# PMSM_G474.net
KiCad netlist of a schematic drawn in Altium Designer
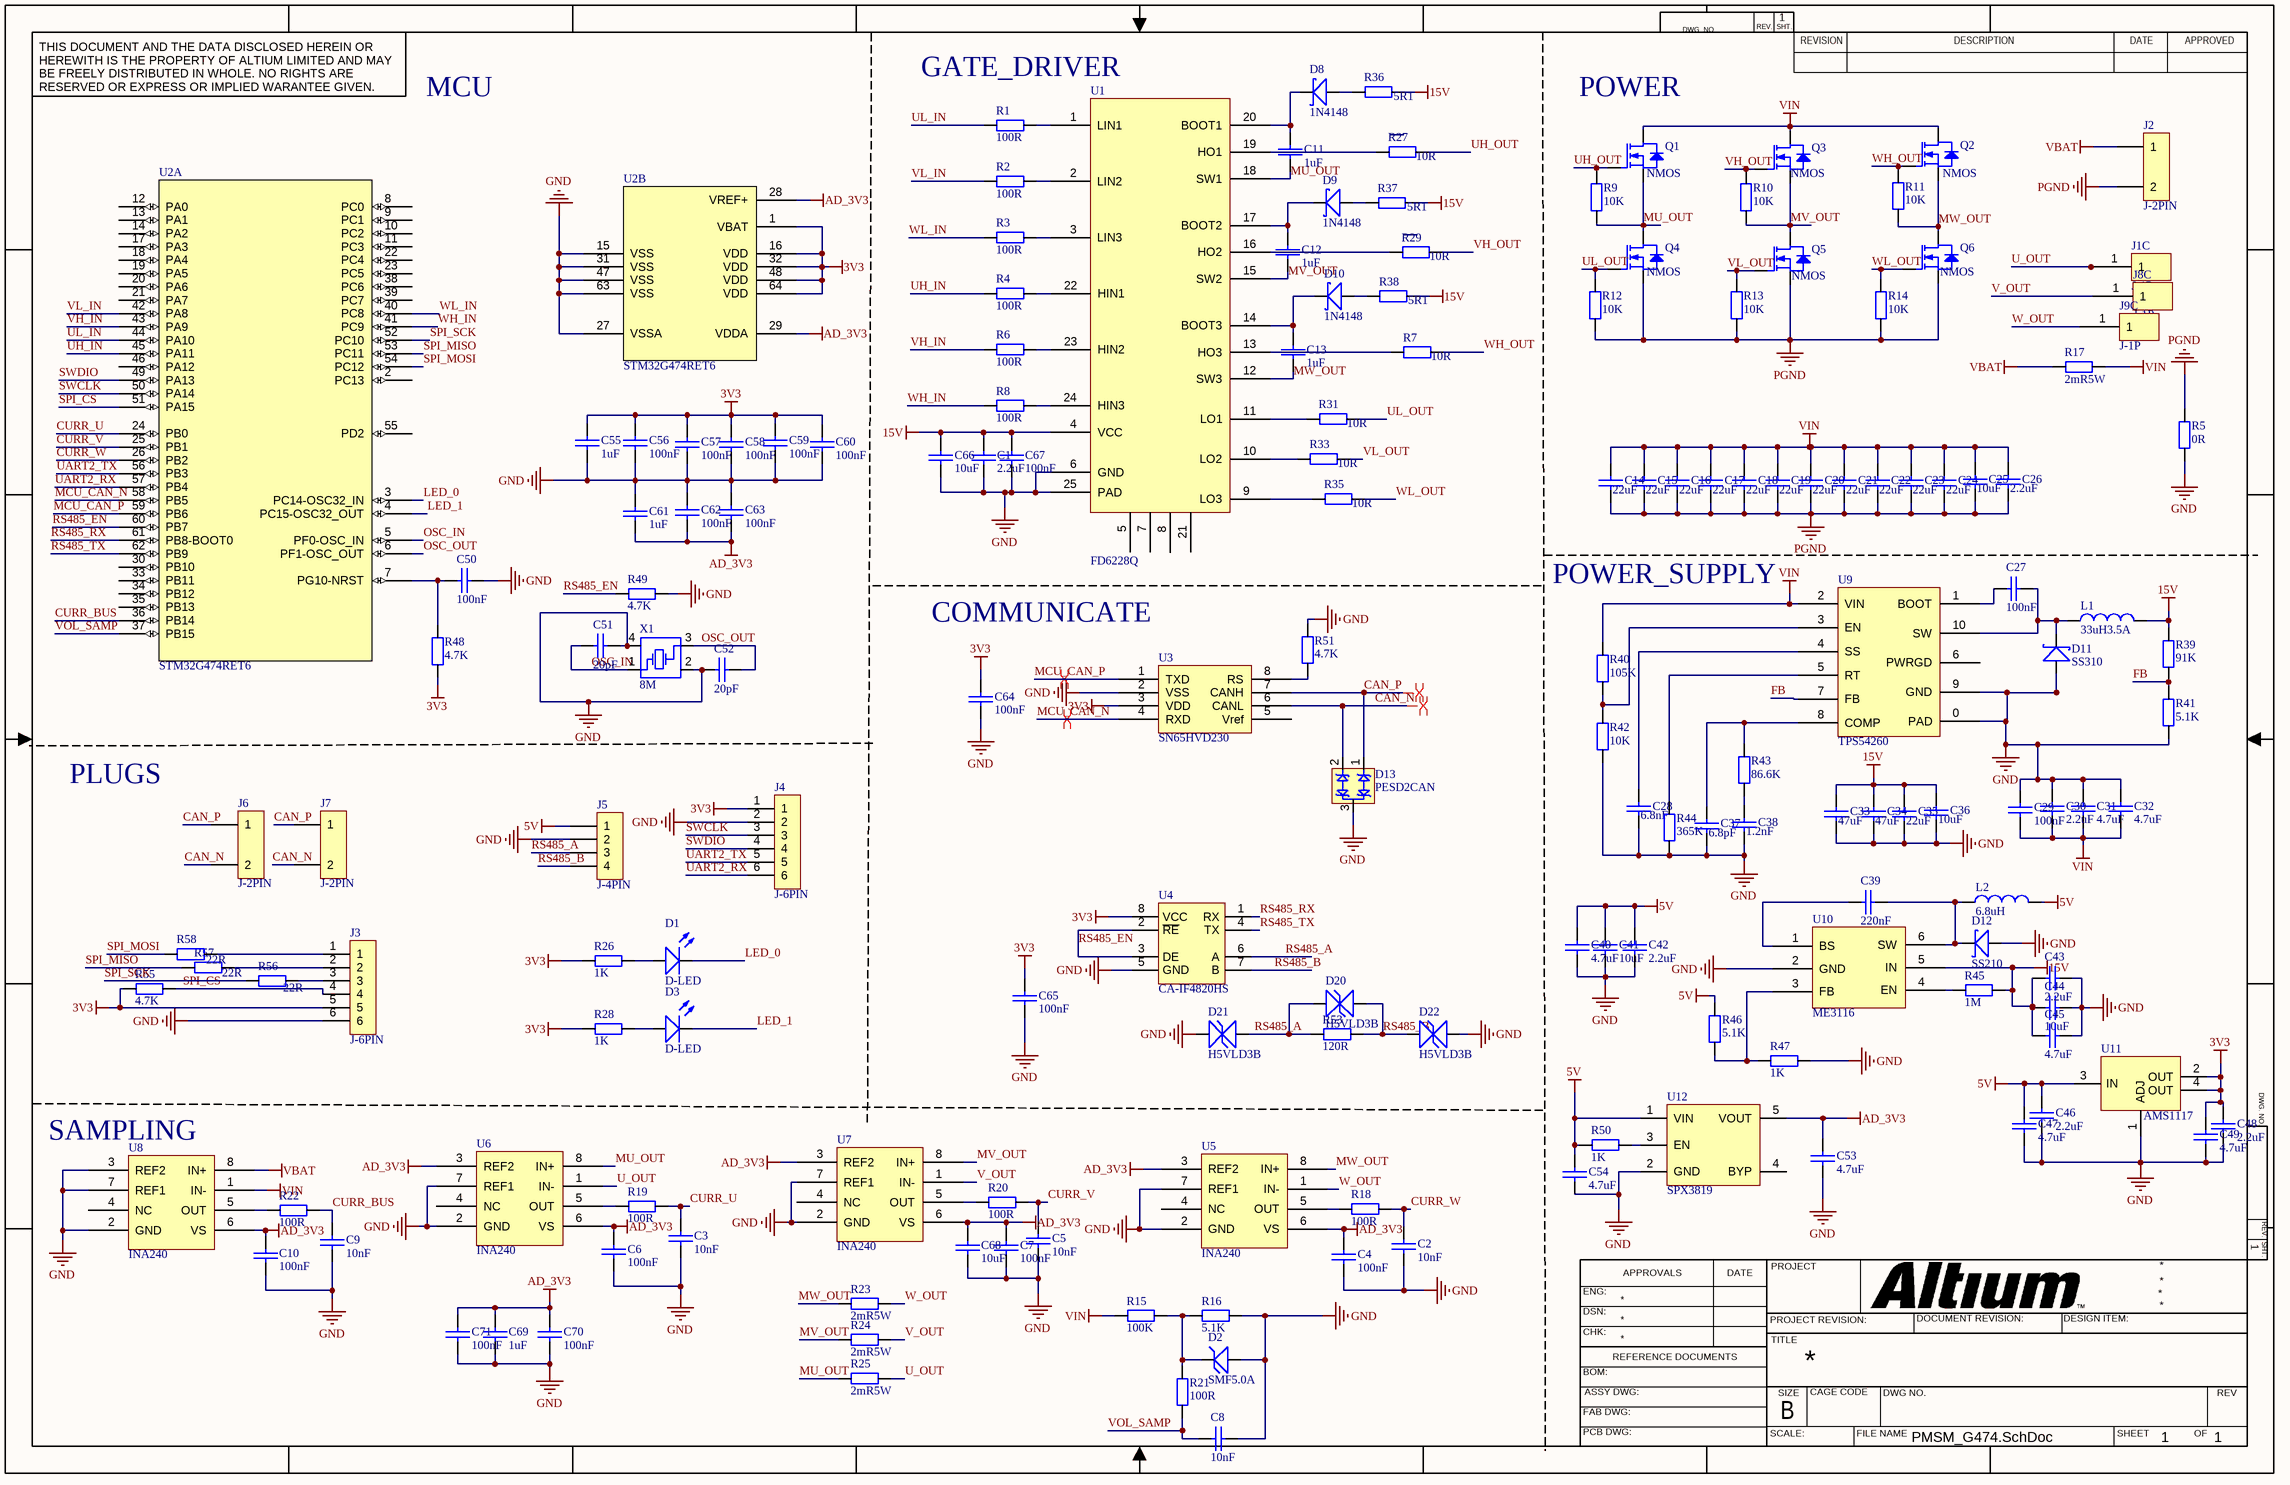
[diagram p0: PMSM_G474.SchDoc]

(export (version "E")
  (design (tool "Eeschema 10.0.6"))
  (components
    (comp (ref "C1")
      (value "2.2uF")
      (footprint "C-0603")
      (description "Non Polarised")
      (libsource (lib "ACTION_SchematicDiagramPack") (part "C"))
    )
    (comp (ref "C2")
      (value "10nF")
      (footprint "C-0603")
      (description "Non Polarised")
      (libsource (lib "ACTION_SchematicDiagramPack") (part "C"))
    )
    (comp (ref "C3")
      (value "10nF")
      (footprint "C-0603")
      (description "Non Polarised")
      (libsource (lib "ACTION_SchematicDiagramPack") (part "C"))
    )
    (comp (ref "C4")
      (value "100nF")
      (footprint "C-0603")
      (description "Non Polarised")
      (libsource (lib "ACTION_SchematicDiagramPack") (part "C"))
    )
    (comp (ref "C5")
      (value "10nF")
      (footprint "C-0603")
      (description "Non Polarised")
      (libsource (lib "ACTION_SchematicDiagramPack") (part "C"))
    )
    (comp (ref "C6")
      (value "100nF")
      (footprint "C-0603")
      (description "Non Polarised")
      (libsource (lib "ACTION_SchematicDiagramPack") (part "C"))
    )
    (comp (ref "C7")
      (value "100nF")
      (footprint "C-0603")
      (description "Non Polarised")
      (libsource (lib "ACTION_SchematicDiagramPack") (part "C"))
    )
    (comp (ref "C8")
      (value "10nF")
      (footprint "C-0603")
      (description "Non Polarised")
      (libsource (lib "ACTION_SchematicDiagramPack") (part "C"))
    )
    (comp (ref "C9")
      (value "10nF")
      (footprint "C-0603")
      (description "Non Polarised")
      (libsource (lib "ACTION_SchematicDiagramPack") (part "C"))
    )
    (comp (ref "C10")
      (value "100nF")
      (footprint "C-0603")
      (description "Non Polarised")
      (libsource (lib "ACTION_SchematicDiagramPack") (part "C"))
    )
    (comp (ref "C11")
      (value "1uF")
      (footprint "C-0603")
      (description "Non Polarised")
      (libsource (lib "ACTION_SchematicDiagramPack") (part "C"))
    )
    (comp (ref "C12")
      (value "1uF")
      (footprint "C-0603")
      (description "Non Polarised")
      (libsource (lib "ACTION_SchematicDiagramPack") (part "C"))
    )
    (comp (ref "C13")
      (value "1uF")
      (footprint "C-0603")
      (description "Non Polarised")
      (libsource (lib "ACTION_SchematicDiagramPack") (part "C"))
    )
    (comp (ref "C14")
      (value "22uF")
      (footprint "C-1206")
      (description "Non Polarised")
      (libsource (lib "ACTION_SchematicDiagramPack") (part "C"))
    )
    (comp (ref "C15")
      (value "22uF")
      (footprint "C-1206")
      (description "Non Polarised")
      (libsource (lib "ACTION_SchematicDiagramPack") (part "C"))
    )
    (comp (ref "C16")
      (value "22uF")
      (footprint "C-1206")
      (description "Non Polarised")
      (libsource (lib "ACTION_SchematicDiagramPack") (part "C"))
    )
    (comp (ref "C17")
      (value "22uF")
      (footprint "C-1206")
      (description "Non Polarised")
      (libsource (lib "ACTION_SchematicDiagramPack") (part "C"))
    )
    (comp (ref "C18")
      (value "22uF")
      (footprint "C-1206")
      (description "Non Polarised")
      (libsource (lib "ACTION_SchematicDiagramPack") (part "C"))
    )
    (comp (ref "C19")
      (value "22uF")
      (footprint "C-1206")
      (description "Non Polarised")
      (libsource (lib "ACTION_SchematicDiagramPack") (part "C"))
    )
    (comp (ref "C20")
      (value "22uF")
      (footprint "C-1206")
      (description "Non Polarised")
      (libsource (lib "ACTION_SchematicDiagramPack") (part "C"))
    )
    (comp (ref "C21")
      (value "22uF")
      (footprint "C-1206")
      (description "Non Polarised")
      (libsource (lib "ACTION_SchematicDiagramPack") (part "C"))
    )
    (comp (ref "C22")
      (value "22uF")
      (footprint "C-1206")
      (description "Non Polarised")
      (libsource (lib "ACTION_SchematicDiagramPack") (part "C"))
    )
    (comp (ref "C23")
      (value "22uF")
      (footprint "C-1206")
      (description "Non Polarised")
      (libsource (lib "ACTION_SchematicDiagramPack") (part "C"))
    )
    (comp (ref "C24")
      (value "22uF")
      (footprint "C-1206")
      (description "Non Polarised")
      (libsource (lib "ACTION_SchematicDiagramPack") (part "C"))
    )
    (comp (ref "C25")
      (value "10uF")
      (footprint "C-1206")
      (description "Non Polarised")
      (libsource (lib "ACTION_SchematicDiagramPack") (part "C"))
    )
    (comp (ref "C26")
      (value "2.2uF")
      (footprint "C-1206")
      (description "Non Polarised")
      (libsource (lib "ACTION_SchematicDiagramPack") (part "C"))
    )
    (comp (ref "C27")
      (value "100nF")
      (footprint "C-0603")
      (description "Non Polarised")
      (libsource (lib "ACTION_SchematicDiagramPack") (part "C"))
    )
    (comp (ref "C28")
      (value "6.8nF")
      (footprint "C-0603")
      (description "Non Polarised")
      (libsource (lib "ACTION_SchematicDiagramPack") (part "C"))
    )
    (comp (ref "C29")
      (value "100nF")
      (footprint "C-0603")
      (description "Non Polarised")
      (libsource (lib "ACTION_SchematicDiagramPack") (part "C"))
    )
    (comp (ref "C30")
      (value "2.2uF")
      (footprint "C-1206")
      (description "Non Polarised")
      (libsource (lib "ACTION_SchematicDiagramPack") (part "C"))
    )
    (comp (ref "C31")
      (value "4.7uF")
      (footprint "C-1206")
      (description "Non Polarised")
      (libsource (lib "ACTION_SchematicDiagramPack") (part "C"))
    )
    (comp (ref "C32")
      (value "4.7uF")
      (footprint "C-1206")
      (description "Non Polarised")
      (libsource (lib "ACTION_SchematicDiagramPack") (part "C"))
    )
    (comp (ref "C33")
      (value "47uF")
      (footprint "C-1206")
      (description "Non Polarised")
      (libsource (lib "ACTION_SchematicDiagramPack") (part "C"))
    )
    (comp (ref "C34")
      (value "47uF")
      (footprint "C-1206")
      (description "Non Polarised")
      (libsource (lib "ACTION_SchematicDiagramPack") (part "C"))
    )
    (comp (ref "C35")
      (value "22uF")
      (footprint "C-1206")
      (description "Non Polarised")
      (libsource (lib "ACTION_SchematicDiagramPack") (part "C"))
    )
    (comp (ref "C36")
      (value "10uF")
      (footprint "C-1206")
      (description "Non Polarised")
      (libsource (lib "ACTION_SchematicDiagramPack") (part "C"))
    )
    (comp (ref "C37")
      (value "6.8pF")
      (footprint "C-0603")
      (description "Non Polarised")
      (libsource (lib "ACTION_SchematicDiagramPack") (part "C"))
    )
    (comp (ref "C38")
      (value "1.2nF")
      (footprint "C-0603")
      (description "Non Polarised")
      (libsource (lib "ACTION_SchematicDiagramPack") (part "C"))
    )
    (comp (ref "C39")
      (value "220nF")
      (footprint "C-0603")
      (description "Non Polarised")
      (libsource (lib "ACTION_SchematicDiagramPack") (part "C"))
    )
    (comp (ref "C40")
      (value "4.7uF")
      (footprint "C-1206")
      (description "Non Polarised")
      (libsource (lib "ACTION_SchematicDiagramPack") (part "C"))
    )
    (comp (ref "C41")
      (value "10uF")
      (footprint "C-1206")
      (description "Non Polarised")
      (libsource (lib "ACTION_SchematicDiagramPack") (part "C"))
    )
    (comp (ref "C42")
      (value "2.2uF")
      (footprint "C-1206")
      (description "Non Polarised")
      (libsource (lib "ACTION_SchematicDiagramPack") (part "C"))
    )
    (comp (ref "C43")
      (value "2.2uF")
      (footprint "C-1206")
      (description "Non Polarised")
      (libsource (lib "ACTION_SchematicDiagramPack") (part "C"))
    )
    (comp (ref "C44")
      (value "10uF")
      (footprint "C-1206")
      (description "Non Polarised")
      (libsource (lib "ACTION_SchematicDiagramPack") (part "C"))
    )
    (comp (ref "C45")
      (value "4.7uF")
      (footprint "C-1206")
      (description "Non Polarised")
      (libsource (lib "ACTION_SchematicDiagramPack") (part "C"))
    )
    (comp (ref "C46")
      (value "2.2uF")
      (footprint "C-0603")
      (description "Non Polarised")
      (libsource (lib "ACTION_SchematicDiagramPack") (part "C"))
    )
    (comp (ref "C47")
      (value "4.7uF")
      (footprint "C-0603")
      (description "Non Polarised")
      (libsource (lib "ACTION_SchematicDiagramPack") (part "C"))
    )
    (comp (ref "C48")
      (value "2.2uF")
      (footprint "C-0603")
      (description "Non Polarised")
      (libsource (lib "ACTION_SchematicDiagramPack") (part "C"))
    )
    (comp (ref "C49")
      (value "4.7uF")
      (footprint "C-0603")
      (description "Non Polarised")
      (libsource (lib "ACTION_SchematicDiagramPack") (part "C"))
    )
    (comp (ref "C50")
      (value "100nF")
      (footprint "C-0603")
      (description "Non Polarised")
      (libsource (lib "ACTION_SchematicDiagramPack") (part "C"))
    )
    (comp (ref "C51")
      (value "20pF")
      (footprint "C-0603")
      (description "Non Polarised")
      (libsource (lib "ACTION_SchematicDiagramPack") (part "C"))
    )
    (comp (ref "C52")
      (value "20pF")
      (footprint "C-0603")
      (description "Non Polarised")
      (libsource (lib "ACTION_SchematicDiagramPack") (part "C"))
    )
    (comp (ref "C53")
      (value "4.7uF")
      (footprint "C-0603")
      (description "Non Polarised")
      (libsource (lib "ACTION_SchematicDiagramPack") (part "C"))
    )
    (comp (ref "C54")
      (value "4.7uF")
      (footprint "C-0603")
      (description "Non Polarised")
      (libsource (lib "ACTION_SchematicDiagramPack") (part "C"))
    )
    (comp (ref "C55")
      (value "1uF")
      (footprint "C-0603")
      (description "Non Polarised")
      (libsource (lib "ACTION_SchematicDiagramPack") (part "C"))
    )
    (comp (ref "C56")
      (value "100nF")
      (footprint "C-0603")
      (description "Non Polarised")
      (libsource (lib "ACTION_SchematicDiagramPack") (part "C"))
    )
    (comp (ref "C57")
      (value "100nF")
      (footprint "C-0603")
      (description "Non Polarised")
      (libsource (lib "ACTION_SchematicDiagramPack") (part "C"))
    )
    (comp (ref "C58")
      (value "100nF")
      (footprint "C-0603")
      (description "Non Polarised")
      (libsource (lib "ACTION_SchematicDiagramPack") (part "C"))
    )
    (comp (ref "C59")
      (value "100nF")
      (footprint "C-0603")
      (description "Non Polarised")
      (libsource (lib "ACTION_SchematicDiagramPack") (part "C"))
    )
    (comp (ref "C60")
      (value "100nF")
      (footprint "C-0603")
      (description "Non Polarised")
      (libsource (lib "ACTION_SchematicDiagramPack") (part "C"))
    )
    (comp (ref "C61")
      (value "1uF")
      (footprint "C-0603")
      (description "Non Polarised")
      (libsource (lib "ACTION_SchematicDiagramPack") (part "C"))
    )
    (comp (ref "C62")
      (value "100nF")
      (footprint "C-0603")
      (description "Non Polarised")
      (libsource (lib "ACTION_SchematicDiagramPack") (part "C"))
    )
    (comp (ref "C63")
      (value "100nF")
      (footprint "C-0603")
      (description "Non Polarised")
      (libsource (lib "ACTION_SchematicDiagramPack") (part "C"))
    )
    (comp (ref "C64")
      (value "100nF")
      (footprint "C-0603")
      (description "Non Polarised")
      (libsource (lib "ACTION_SchematicDiagramPack") (part "C"))
    )
    (comp (ref "C65")
      (value "100nF")
      (footprint "C-0603")
      (description "Non Polarised")
      (libsource (lib "ACTION_SchematicDiagramPack") (part "C"))
    )
    (comp (ref "C66")
      (value "10uF")
      (footprint "C-0603")
      (description "Non Polarised")
      (libsource (lib "ACTION_SchematicDiagramPack") (part "C"))
    )
    (comp (ref "C67")
      (value "100nF")
      (footprint "C-0603")
      (description "Non Polarised")
      (libsource (lib "ACTION_SchematicDiagramPack") (part "C"))
    )
    (comp (ref "C68")
      (value "10uF")
      (footprint "C-0603")
      (description "Non Polarised")
      (libsource (lib "ACTION_SchematicDiagramPack") (part "C"))
    )
    (comp (ref "C69")
      (value "1uF")
      (footprint "C-0603")
      (description "Non Polarised")
      (libsource (lib "ACTION_SchematicDiagramPack") (part "C"))
    )
    (comp (ref "C70")
      (value "100nF")
      (footprint "C-0603")
      (description "Non Polarised")
      (libsource (lib "ACTION_SchematicDiagramPack") (part "C"))
    )
    (comp (ref "C71")
      (value "100nF")
      (footprint "C-0603")
      (description "Non Polarised")
      (libsource (lib "ACTION_SchematicDiagramPack") (part "C"))
    )
    (comp (ref "D1")
      (value "D-LED")
      (footprint "D-LED-0603Blue")
      (description "LED")
      (libsource (lib "ACTION_SchematicDiagramPack") (part "D-LED"))
    )
    (comp (ref "D2")
      (value "SMF5.0A")
      (footprint "D-SOD-123")
      (description "单向TVS")
      (libsource (lib "ACTION_SchematicDiagramPack") (part "D-TVS-U"))
    )
    (comp (ref "D3")
      (value "D-LED")
      (footprint "D-LED-0603Blue")
      (description "LED")
      (libsource (lib "ACTION_SchematicDiagramPack") (part "D-LED"))
    )
    (comp (ref "D8")
      (value "1N4148")
      (footprint "D-SOD-123")
      (description "Schottky")
      (libsource (lib "ACTION_SchematicDiagramPack") (part "D-Schottky"))
    )
    (comp (ref "D9")
      (value "1N4148")
      (footprint "D-SOD-123")
      (description "Schottky")
      (libsource (lib "ACTION_SchematicDiagramPack") (part "D-Schottky"))
    )
    (comp (ref "D10")
      (value "1N4148")
      (footprint "D-SOD-123")
      (description "Schottky")
      (libsource (lib "ACTION_SchematicDiagramPack") (part "D-Schottky"))
    )
    (comp (ref "D11")
      (value "SS310")
      (footprint "DO-214AC(SMA)")
      (description "Schottky")
      (libsource (lib "ACTION_SchematicDiagramPack") (part "D-Schottky"))
    )
    (comp (ref "D12")
      (value "SS210")
      (footprint "DO-214AC(SMA)")
      (description "Schottky")
      (libsource (lib "ACTION_SchematicDiagramPack") (part "D-Schottky"))
    )
    (comp (ref "D13")
      (value "PESD2CAN")
      (footprint "SOT-233")
      (description "组合ESD二极管")
      (libsource (lib "ACTION_SchematicDiagramPack") (part "D-ESD"))
    )
    (comp (ref "D20")
      (value "H5VLD3B")
      (footprint "D-SOD-323")
      (description "双向TVS")
      (libsource (lib "ACTION_SchematicDiagramPack") (part "D-TVS-B"))
    )
    (comp (ref "D21")
      (value "H5VLD3B")
      (footprint "D-SOD-323")
      (description "双向TVS")
      (libsource (lib "ACTION_SchematicDiagramPack") (part "D-TVS-B"))
    )
    (comp (ref "D22")
      (value "H5VLD3B")
      (footprint "D-SOD-323")
      (description "双向TVS")
      (libsource (lib "ACTION_SchematicDiagramPack") (part "D-TVS-B"))
    )
    (comp (ref "J1")
      (value "J-1P")
      (footprint "PAD-1")
      (libsource (lib "ACTION_SchematicDiagramPack") (part "J-1P"))
    )
    (comp (ref "J2")
      (value "J-2PIN")
      (footprint "J-XT30-2P-F")
      (libsource (lib "ACTION_SchematicDiagramPack") (part "J-2PIN"))
    )
    (comp (ref "J3")
      (value "J-6PIN")
      (footprint "J-GH-6P")
      (libsource (lib "ACTION_SchematicDiagramPack") (part "J-6PIN"))
    )
    (comp (ref "J4")
      (value "J-6PIN")
      (footprint "J-GH-6P")
      (libsource (lib "ACTION_SchematicDiagramPack") (part "J-6PIN"))
    )
    (comp (ref "J5")
      (value "J-4PIN")
      (footprint "J-GH-4P")
      (fields (field (name "PUBLISHER") "Altium Limited"))
      (libsource (lib "ACTION_SchematicDiagramPack") (part "J-4PIN"))
    )
    (comp (ref "J6")
      (value "J-2PIN")
      (footprint "J-GH-2P")
      (libsource (lib "ACTION_SchematicDiagramPack") (part "J-2PIN"))
    )
    (comp (ref "J7")
      (value "J-2PIN")
      (footprint "J-GH-2P")
      (libsource (lib "ACTION_SchematicDiagramPack") (part "J-2PIN"))
    )
    (comp (ref "J8")
      (value "J-1P")
      (footprint "PAD-1")
      (libsource (lib "ACTION_SchematicDiagramPack") (part "J-1P"))
    )
    (comp (ref "J9")
      (value "J-1P")
      (footprint "PAD-1")
      (libsource (lib "ACTION_SchematicDiagramPack") (part "J-1P"))
    )
    (comp (ref "L1")
      (value "33uH3.5A")
      (footprint "L-SMD-7.0*7.0")
      (description "Inductor")
      (libsource (lib "ACTION_SchematicDiagramPack") (part "L-SMD"))
    )
    (comp (ref "L2")
      (value "6.8uH")
      (footprint "L-SMD-5.0*5.0*4.0")
      (description "Inductor")
      (libsource (lib "ACTION_SchematicDiagramPack") (part "L-SMD"))
    )
    (comp (ref "Q1")
      (value "NMOS")
      (footprint "SO-8FL  5*6")
      (libsource (lib "ACTION_SchematicDiagramPack") (part "NMOS"))
    )
    (comp (ref "Q2")
      (value "NMOS")
      (footprint "SO-8FL  5*6")
      (libsource (lib "ACTION_SchematicDiagramPack") (part "NMOS"))
    )
    (comp (ref "Q3")
      (value "NMOS")
      (footprint "SO-8FL  5*6")
      (libsource (lib "ACTION_SchematicDiagramPack") (part "NMOS"))
    )
    (comp (ref "Q4")
      (value "NMOS")
      (footprint "SO-8FL  5*6")
      (libsource (lib "ACTION_SchematicDiagramPack") (part "NMOS"))
    )
    (comp (ref "Q5")
      (value "NMOS")
      (footprint "SO-8FL  5*6")
      (libsource (lib "ACTION_SchematicDiagramPack") (part "NMOS"))
    )
    (comp (ref "Q6")
      (value "NMOS")
      (footprint "SO-8FL  5*6")
      (libsource (lib "ACTION_SchematicDiagramPack") (part "NMOS"))
    )
    (comp (ref "R1")
      (value "100R")
      (footprint "R-0603")
      (description "Resistor")
      (libsource (lib "ACTION_SchematicDiagramPack") (part "R"))
    )
    (comp (ref "R2")
      (value "100R")
      (footprint "R-0603")
      (description "Resistor")
      (libsource (lib "ACTION_SchematicDiagramPack") (part "R"))
    )
    (comp (ref "R3")
      (value "100R")
      (footprint "R-0603")
      (description "Resistor")
      (libsource (lib "ACTION_SchematicDiagramPack") (part "R"))
    )
    (comp (ref "R4")
      (value "100R")
      (footprint "R-0603")
      (description "Resistor")
      (libsource (lib "ACTION_SchematicDiagramPack") (part "R"))
    )
    (comp (ref "R5")
      (value "0R")
      (footprint "R-0603")
      (description "Resistor")
      (libsource (lib "ACTION_SchematicDiagramPack") (part "R"))
    )
    (comp (ref "R6")
      (value "100R")
      (footprint "R-0603")
      (description "Resistor")
      (libsource (lib "ACTION_SchematicDiagramPack") (part "R"))
    )
    (comp (ref "R7")
      (value "10R")
      (footprint "R-0603")
      (description "Resistor")
      (libsource (lib "ACTION_SchematicDiagramPack") (part "R"))
    )
    (comp (ref "R8")
      (value "100R")
      (footprint "R-0603")
      (description "Resistor")
      (libsource (lib "ACTION_SchematicDiagramPack") (part "R"))
    )
    (comp (ref "R9")
      (value "10K")
      (footprint "R-0603")
      (description "Resistor")
      (libsource (lib "ACTION_SchematicDiagramPack") (part "R"))
    )
    (comp (ref "R10")
      (value "10K")
      (footprint "R-0603")
      (description "Resistor")
      (libsource (lib "ACTION_SchematicDiagramPack") (part "R"))
    )
    (comp (ref "R11")
      (value "10K")
      (footprint "R-0603")
      (description "Resistor")
      (libsource (lib "ACTION_SchematicDiagramPack") (part "R"))
    )
    (comp (ref "R12")
      (value "10K")
      (footprint "R-0603")
      (description "Resistor")
      (libsource (lib "ACTION_SchematicDiagramPack") (part "R"))
    )
    (comp (ref "R13")
      (value "10K")
      (footprint "R-0603")
      (description "Resistor")
      (libsource (lib "ACTION_SchematicDiagramPack") (part "R"))
    )
    (comp (ref "R14")
      (value "10K")
      (footprint "R-0603")
      (description "Resistor")
      (libsource (lib "ACTION_SchematicDiagramPack") (part "R"))
    )
    (comp (ref "R15")
      (value "100K")
      (footprint "R-0603")
      (description "Resistor")
      (libsource (lib "ACTION_SchematicDiagramPack") (part "R"))
    )
    (comp (ref "R16")
      (value "5.1K")
      (footprint "R-0603")
      (description "Resistor")
      (libsource (lib "ACTION_SchematicDiagramPack") (part "R"))
    )
    (comp (ref "R17")
      (value "2mR5W")
      (footprint "R-2512")
      (description "Resistor")
      (libsource (lib "ACTION_SchematicDiagramPack") (part "R"))
    )
    (comp (ref "R18")
      (value "100R")
      (footprint "R-0603")
      (description "Resistor")
      (libsource (lib "ACTION_SchematicDiagramPack") (part "R"))
    )
    (comp (ref "R19")
      (value "100R")
      (footprint "R-0603")
      (description "Resistor")
      (libsource (lib "ACTION_SchematicDiagramPack") (part "R"))
    )
    (comp (ref "R20")
      (value "100R")
      (footprint "R-0603")
      (description "Resistor")
      (libsource (lib "ACTION_SchematicDiagramPack") (part "R"))
    )
    (comp (ref "R21")
      (value "100R")
      (footprint "R-0603")
      (description "Resistor")
      (libsource (lib "ACTION_SchematicDiagramPack") (part "R"))
    )
    (comp (ref "R22")
      (value "100R")
      (footprint "R-0603")
      (description "Resistor")
      (libsource (lib "ACTION_SchematicDiagramPack") (part "R"))
    )
    (comp (ref "R23")
      (value "2mR5W")
      (footprint "R-2512")
      (description "Resistor")
      (libsource (lib "ACTION_SchematicDiagramPack") (part "R"))
    )
    (comp (ref "R24")
      (value "2mR5W")
      (footprint "R-2512")
      (description "Resistor")
      (libsource (lib "ACTION_SchematicDiagramPack") (part "R"))
    )
    (comp (ref "R25")
      (value "2mR5W")
      (footprint "R-2512")
      (description "Resistor")
      (libsource (lib "ACTION_SchematicDiagramPack") (part "R"))
    )
    (comp (ref "R26")
      (value "1K")
      (footprint "R-0603")
      (description "Resistor")
      (libsource (lib "ACTION_SchematicDiagramPack") (part "R"))
    )
    (comp (ref "R27")
      (value "10R")
      (footprint "R-0603")
      (description "Resistor")
      (libsource (lib "ACTION_SchematicDiagramPack") (part "R"))
    )
    (comp (ref "R28")
      (value "1K")
      (footprint "R-0603")
      (description "Resistor")
      (libsource (lib "ACTION_SchematicDiagramPack") (part "R"))
    )
    (comp (ref "R29")
      (value "10R")
      (footprint "R-0603")
      (description "Resistor")
      (libsource (lib "ACTION_SchematicDiagramPack") (part "R"))
    )
    (comp (ref "R31")
      (value "10R")
      (footprint "R-0603")
      (description "Resistor")
      (libsource (lib "ACTION_SchematicDiagramPack") (part "R"))
    )
    (comp (ref "R33")
      (value "10R")
      (footprint "R-0603")
      (description "Resistor")
      (libsource (lib "ACTION_SchematicDiagramPack") (part "R"))
    )
    (comp (ref "R35")
      (value "10R")
      (footprint "R-0603")
      (description "Resistor")
      (libsource (lib "ACTION_SchematicDiagramPack") (part "R"))
    )
    (comp (ref "R36")
      (value "5R1")
      (footprint "R-0603")
      (description "Resistor")
      (libsource (lib "ACTION_SchematicDiagramPack") (part "R"))
    )
    (comp (ref "R37")
      (value "5R1")
      (footprint "R-0603")
      (description "Resistor")
      (libsource (lib "ACTION_SchematicDiagramPack") (part "R"))
    )
    (comp (ref "R38")
      (value "5R1")
      (footprint "R-0603")
      (description "Resistor")
      (libsource (lib "ACTION_SchematicDiagramPack") (part "R"))
    )
    (comp (ref "R39")
      (value "91K")
      (footprint "R-0603")
      (description "Resistor")
      (libsource (lib "ACTION_SchematicDiagramPack") (part "R"))
    )
    (comp (ref "R40")
      (value "105K")
      (footprint "R-0603")
      (description "Resistor")
      (libsource (lib "ACTION_SchematicDiagramPack") (part "R"))
    )
    (comp (ref "R41")
      (value "5.1K")
      (footprint "R-0603")
      (description "Resistor")
      (libsource (lib "ACTION_SchematicDiagramPack") (part "R"))
    )
    (comp (ref "R42")
      (value "10K")
      (footprint "R-0603")
      (description "Resistor")
      (libsource (lib "ACTION_SchematicDiagramPack") (part "R"))
    )
    (comp (ref "R43")
      (value "86.6K")
      (footprint "R-0603")
      (description "Resistor")
      (libsource (lib "ACTION_SchematicDiagramPack") (part "R"))
    )
    (comp (ref "R44")
      (value "365K")
      (footprint "R-0603")
      (description "Resistor")
      (libsource (lib "ACTION_SchematicDiagramPack") (part "R"))
    )
    (comp (ref "R45")
      (value "1M")
      (footprint "R-0603")
      (description "Resistor")
      (libsource (lib "ACTION_SchematicDiagramPack") (part "R"))
    )
    (comp (ref "R46")
      (value "5.1K")
      (footprint "R-0603")
      (description "Resistor")
      (libsource (lib "ACTION_SchematicDiagramPack") (part "R"))
    )
    (comp (ref "R47")
      (value "1K")
      (footprint "R-0603")
      (description "Resistor")
      (libsource (lib "ACTION_SchematicDiagramPack") (part "R"))
    )
    (comp (ref "R48")
      (value "4.7K")
      (footprint "R-0603")
      (description "Resistor")
      (libsource (lib "ACTION_SchematicDiagramPack") (part "R"))
    )
    (comp (ref "R49")
      (value "4.7K")
      (footprint "R-0603")
      (description "Resistor")
      (libsource (lib "ACTION_SchematicDiagramPack") (part "R"))
    )
    (comp (ref "R50")
      (value "1K")
      (footprint "R-0603")
      (description "Resistor")
      (libsource (lib "ACTION_SchematicDiagramPack") (part "R"))
    )
    (comp (ref "R51")
      (value "4.7K")
      (footprint "R-0603")
      (description "Resistor")
      (libsource (lib "ACTION_SchematicDiagramPack") (part "R"))
    )
    (comp (ref "R53")
      (value "120R")
      (footprint "R-0603")
      (description "Resistor")
      (libsource (lib "ACTION_SchematicDiagramPack") (part "R"))
    )
    (comp (ref "R55")
      (value "4.7K")
      (footprint "R-0603")
      (description "Resistor")
      (libsource (lib "ACTION_SchematicDiagramPack") (part "R"))
    )
    (comp (ref "R56")
      (value "22R")
      (footprint "R-0603")
      (description "Resistor")
      (libsource (lib "ACTION_SchematicDiagramPack") (part "R"))
    )
    (comp (ref "R57")
      (value "22R")
      (footprint "R-0603")
      (description "Resistor")
      (libsource (lib "ACTION_SchematicDiagramPack") (part "R"))
    )
    (comp (ref "R58")
      (value "22R")
      (footprint "R-0603")
      (description "Resistor")
      (libsource (lib "ACTION_SchematicDiagramPack") (part "R"))
    )
    (comp (ref "U1")
      (value "FD6228Q")
      (footprint "QFN-24-4X4")
      (description "三相栅极驱动器")
      (libsource (lib "ACTION_SchematicDiagramPack") (part "FD6228Q"))
    )
    (comp (ref "U2")
      (value "STM32G474RET6")
      (footprint "STM-LQFP64_N")
      (libsource (lib "ACTION_SchematicDiagramPack") (part "STM32G474RET6"))
    )
    (comp (ref "U3")
      (value "SN65HVD230")
      (footprint "SOp-8")
      (libsource (lib "ACTION_SchematicDiagramPack") (part "SN65HVD230"))
    )
    (comp (ref "U4")
      (value "CA-IF4820HS")
      (footprint "SOIC-8(4mm)")
      (description "485 半双工 非隔离 ±15V共模 50M")
      (libsource (lib "ACTION_SchematicDiagramPack") (part "CA-IF4820HS"))
    )
    (comp (ref "U5")
      (value "INA240")
      (footprint "SOIC-8(4mm)")
      (description "具有PWM抑制功能的电流检测IC")
      (libsource (lib "ACTION_SchematicDiagramPack") (part "INA240"))
    )
    (comp (ref "U6")
      (value "INA240")
      (footprint "SOIC-8(4mm)")
      (description "具有PWM抑制功能的电流检测IC")
      (libsource (lib "ACTION_SchematicDiagramPack") (part "INA240"))
    )
    (comp (ref "U7")
      (value "INA240")
      (footprint "SOIC-8(4mm)")
      (description "具有PWM抑制功能的电流检测IC")
      (libsource (lib "ACTION_SchematicDiagramPack") (part "INA240"))
    )
    (comp (ref "U8")
      (value "INA240")
      (footprint "SOIC-8(4mm)")
      (description "具有PWM抑制功能的电流检测IC")
      (libsource (lib "ACTION_SchematicDiagramPack") (part "INA240"))
    )
    (comp (ref "U9")
      (value "TPS54260")
      (footprint "MSOP-10")
      (description "3.5V-60V 2A Step-Down DCDC Convertor")
      (libsource (lib "ACTION_SchematicDiagramPack") (part "TPS54260"))
    )
    (comp (ref "U10")
      (value "ME3116")
      (footprint "SOT-236")
      (description "DC-DC BUCK CONVERTER 40V VINmax 1A IOUTmax")
      (libsource (lib "ACTION_SchematicDiagramPack") (part "ME3116"))
    )
    (comp (ref "U11")
      (value "AMS1117")
      (footprint "SOT-89")
      (description "LDO")
      (libsource (lib "ACTION_SchematicDiagramPack") (part "AMS1117"))
    )
    (comp (ref "U12")
      (value "SPX3819")
      (footprint "SOT-235")
      (description "LDO")
      (libsource (lib "ACTION_SchematicDiagramPack") (part "SPX3819"))
    )
    (comp (ref "X1")
      (value "8M")
      (footprint "X-SMD-3225-4P")
      (description "Crystal Oscillator")
      (libsource (lib "ACTION_SchematicDiagramPack") (part "Crystal-4p"))
    )
  )
  (nets
    (net (code "1") (name "/CAN_N") (class "Default")
      (node (ref "D13") (pin "2") (pinfunction "2_2") (pintype "passive"))
      (node (ref "J6") (pin "2") (pinfunction "2_2") (pintype "passive"))
      (node (ref "J7") (pin "2") (pinfunction "2_2") (pintype "passive"))
      (node (ref "U3") (pin "6") (pinfunction "CANL_6") (pintype "passive"))
    )
    (net (code "2") (name "/CAN_P") (class "Default")
      (node (ref "D13") (pin "1") (pinfunction "1_1") (pintype "passive"))
      (node (ref "J6") (pin "1") (pinfunction "1_1") (pintype "passive"))
      (node (ref "J7") (pin "1") (pinfunction "1_1") (pintype "passive"))
      (node (ref "U3") (pin "7") (pinfunction "CANH_7") (pintype "passive"))
    )
    (net (code "3") (name "/CURR_BUS") (class "Default")
      (node (ref "C9") (pin "1") (pinfunction "1_1") (pintype "passive"))
      (node (ref "R22") (pin "1") (pintype "passive"))
      (node (ref "U2") (pin "36") (pinfunction "PB14_36") (pintype "bidirectional"))
    )
    (net (code "4") (name "/CURR_U") (class "Default")
      (node (ref "C3") (pin "1") (pinfunction "1_1") (pintype "passive"))
      (node (ref "R19") (pin "1") (pintype "passive"))
      (node (ref "U2") (pin "24") (pinfunction "PB0_24") (pintype "bidirectional"))
    )
    (net (code "5") (name "/CURR_V") (class "Default")
      (node (ref "C5") (pin "1") (pinfunction "1_1") (pintype "passive"))
      (node (ref "R20") (pin "1") (pintype "passive"))
      (node (ref "U2") (pin "25") (pinfunction "PB1_25") (pintype "bidirectional"))
    )
    (net (code "6") (name "/CURR_W") (class "Default")
      (node (ref "C2") (pin "1") (pinfunction "1_1") (pintype "passive"))
      (node (ref "R18") (pin "1") (pintype "passive"))
      (node (ref "U2") (pin "26") (pinfunction "PB2_26") (pintype "bidirectional"))
    )
    (net (code "7") (name "/FB") (class "Default")
      (node (ref "R39") (pin "1") (pintype "passive"))
      (node (ref "R41") (pin "2") (pintype "passive"))
      (node (ref "U9") (pin "7") (pinfunction "FB_7") (pintype "passive"))
    )
    (net (code "8") (name "/LED_0") (class "Default")
      (node (ref "D1") (pin "2") (pinfunction "2_2") (pintype "passive"))
      (node (ref "U2") (pin "3") (pinfunction "PC14-OSC32_IN_3") (pintype "bidirectional"))
    )
    (net (code "9") (name "/LED_1") (class "Default")
      (node (ref "D3") (pin "2") (pinfunction "2_2") (pintype "passive"))
      (node (ref "U2") (pin "4") (pinfunction "PC15-OSC32_OUT_4") (pintype "bidirectional"))
    )
    (net (code "10") (name "/MCU_CAN_N") (class "Default")
      (node (ref "U2") (pin "58") (pinfunction "PB5_58") (pintype "bidirectional"))
      (node (ref "U3") (pin "4") (pinfunction "RXD_4") (pintype "passive"))
    )
    (net (code "11") (name "/MCU_CAN_P") (class "Default")
      (node (ref "U2") (pin "59") (pinfunction "PB6_59") (pintype "bidirectional"))
      (node (ref "U3") (pin "1") (pinfunction "TXD_1") (pintype "passive"))
    )
    (net (code "12") (name "/MU_OUT") (class "Default")
      (node (ref "C11") (pin "2") (pinfunction "2_2") (pintype "passive"))
      (node (ref "Q1") (pin "3") (pinfunction "S_3") (pintype "passive"))
      (node (ref "Q4") (pin "2") (pinfunction "D_2") (pintype "passive"))
      (node (ref "R25") (pin "1") (pintype "passive"))
      (node (ref "R9") (pin "2") (pintype "passive"))
      (node (ref "U1") (pin "18") (pinfunction "SW1_18") (pintype "passive"))
      (node (ref "U6") (pin "8") (pinfunction "IN+_8") (pintype "passive"))
    )
    (net (code "13") (name "/MV_OUT") (class "Default")
      (node (ref "C12") (pin "2") (pinfunction "2_2") (pintype "passive"))
      (node (ref "Q3") (pin "3") (pinfunction "S_3") (pintype "passive"))
      (node (ref "Q5") (pin "2") (pinfunction "D_2") (pintype "passive"))
      (node (ref "R10") (pin "2") (pintype "passive"))
      (node (ref "R24") (pin "1") (pintype "passive"))
      (node (ref "U1") (pin "15") (pinfunction "SW2_15") (pintype "passive"))
      (node (ref "U7") (pin "8") (pinfunction "IN+_8") (pintype "passive"))
    )
    (net (code "14") (name "/MW_OUT") (class "Default")
      (node (ref "C13") (pin "2") (pinfunction "2_2") (pintype "passive"))
      (node (ref "Q2") (pin "3") (pinfunction "S_3") (pintype "passive"))
      (node (ref "Q6") (pin "2") (pinfunction "D_2") (pintype "passive"))
      (node (ref "R11") (pin "2") (pintype "passive"))
      (node (ref "R23") (pin "1") (pintype "passive"))
      (node (ref "U1") (pin "12") (pinfunction "SW3_12") (pintype "passive"))
      (node (ref "U5") (pin "8") (pinfunction "IN+_8") (pintype "passive"))
    )
    (net (code "15") (name "/OSC_IN") (class "Default")
      (node (ref "C51") (pin "2") (pinfunction "2_2") (pintype "passive"))
      (node (ref "U2") (pin "5") (pinfunction "PF0-OSC_IN_5") (pintype "bidirectional"))
      (node (ref "X1") (pin "1") (pinfunction "OSC1_1") (pintype "passive"))
    )
    (net (code "16") (name "/OSC_OUT") (class "Default")
      (node (ref "C52") (pin "2") (pinfunction "2_2") (pintype "passive"))
      (node (ref "U2") (pin "6") (pinfunction "PF1-OSC_OUT_6") (pintype "bidirectional"))
      (node (ref "X1") (pin "3") (pinfunction "OSC2_3") (pintype "passive"))
    )
    (net (code "17") (name "/RS485_A") (class "Default")
      (node (ref "D20") (pin "1") (pinfunction "A_1") (pintype "passive"))
      (node (ref "D21") (pin "2") (pinfunction "K_2") (pintype "passive"))
      (node (ref "J5") (pin "3") (pinfunction "3_3") (pintype "passive"))
      (node (ref "R53") (pin "2") (pintype "passive"))
      (node (ref "U4") (pin "6") (pinfunction "A_6") (pintype "passive"))
    )
    (net (code "18") (name "/RS485_B") (class "Default")
      (node (ref "D20") (pin "2") (pinfunction "K_2") (pintype "passive"))
      (node (ref "D22") (pin "2") (pinfunction "K_2") (pintype "passive"))
      (node (ref "J5") (pin "4") (pinfunction "4_4") (pintype "passive"))
      (node (ref "R53") (pin "1") (pintype "passive"))
      (node (ref "U4") (pin "7") (pinfunction "B_7") (pintype "passive"))
    )
    (net (code "19") (name "/RS485_EN") (class "Default")
      (node (ref "R49") (pin "2") (pintype "passive"))
      (node (ref "U2") (pin "60") (pinfunction "PB7_60") (pintype "bidirectional"))
      (node (ref "U4") (pin "2") (pinfunction "~{RE}_2") (pintype "passive"))
      (node (ref "U4") (pin "3") (pinfunction "DE_3") (pintype "passive"))
    )
    (net (code "20") (name "/RS485_RX") (class "Default")
      (node (ref "U2") (pin "61") (pinfunction "PB8-BOOT0_61") (pintype "bidirectional"))
      (node (ref "U4") (pin "1") (pinfunction "RX_1") (pintype "passive"))
    )
    (net (code "21") (name "/RS485_TX") (class "Default")
      (node (ref "U2") (pin "62") (pinfunction "PB9_62") (pintype "bidirectional"))
      (node (ref "U4") (pin "4") (pinfunction "TX_4") (pintype "passive"))
    )
    (net (code "22") (name "/SPI_CS") (class "Default")
      (node (ref "J3") (pin "4") (pinfunction "4_4") (pintype "passive"))
      (node (ref "R55") (pin "1") (pintype "passive"))
      (node (ref "U2") (pin "51") (pinfunction "PA15_51") (pintype "bidirectional"))
    )
    (net (code "23") (name "/SPI_MISO") (class "Default")
      (node (ref "R57") (pin "2") (pintype "passive"))
      (node (ref "U2") (pin "53") (pinfunction "PC11_53") (pintype "bidirectional"))
    )
    (net (code "24") (name "/SPI_MOSI") (class "Default")
      (node (ref "R58") (pin "2") (pintype "passive"))
      (node (ref "U2") (pin "54") (pinfunction "PC12_54") (pintype "bidirectional"))
    )
    (net (code "25") (name "/SPI_SCK") (class "Default")
      (node (ref "R56") (pin "2") (pintype "passive"))
      (node (ref "U2") (pin "52") (pinfunction "PC10_52") (pintype "bidirectional"))
    )
    (net (code "26") (name "/SWCLK") (class "Default")
      (node (ref "J4") (pin "3") (pinfunction "3_3") (pintype "passive"))
      (node (ref "U2") (pin "50") (pinfunction "PA14_50") (pintype "bidirectional"))
    )
    (net (code "27") (name "/SWDIO") (class "Default")
      (node (ref "J4") (pin "4") (pinfunction "4_4") (pintype "passive"))
      (node (ref "U2") (pin "49") (pinfunction "PA13_49") (pintype "bidirectional"))
    )
    (net (code "28") (name "/UART2_RX") (class "Default")
      (node (ref "J4") (pin "6") (pinfunction "6_6") (pintype "passive"))
      (node (ref "U2") (pin "57") (pinfunction "PB4_57") (pintype "bidirectional"))
    )
    (net (code "29") (name "/UART2_TX") (class "Default")
      (node (ref "J4") (pin "5") (pinfunction "5_5") (pintype "passive"))
      (node (ref "U2") (pin "56") (pinfunction "PB3_56") (pintype "bidirectional"))
    )
    (net (code "30") (name "/UH_IN") (class "Default")
      (node (ref "R4") (pin "2") (pintype "passive"))
      (node (ref "U2") (pin "45") (pinfunction "PA11_45") (pintype "bidirectional"))
    )
    (net (code "31") (name "/UH_OUT") (class "Default")
      (node (ref "Q1") (pin "1") (pinfunction "G_1") (pintype "passive"))
      (node (ref "R27") (pin "2") (pintype "passive"))
      (node (ref "R9") (pin "1") (pintype "passive"))
    )
    (net (code "32") (name "/UL_IN") (class "Default")
      (node (ref "R1") (pin "2") (pintype "passive"))
      (node (ref "U2") (pin "44") (pinfunction "PA10_44") (pintype "bidirectional"))
    )
    (net (code "33") (name "/UL_OUT") (class "Default")
      (node (ref "Q4") (pin "1") (pinfunction "G_1") (pintype "passive"))
      (node (ref "R12") (pin "1") (pintype "passive"))
      (node (ref "R31") (pin "2") (pintype "passive"))
    )
    (net (code "34") (name "/U_OUT") (class "Default")
      (node (ref "J1") (pin "1") (pinfunction "1_1") (pintype "passive"))
      (node (ref "R25") (pin "2") (pintype "passive"))
      (node (ref "U6") (pin "1") (pinfunction "IN-_1") (pintype "passive"))
    )
    (net (code "35") (name "/VH_IN") (class "Default")
      (node (ref "R6") (pin "2") (pintype "passive"))
      (node (ref "U2") (pin "43") (pinfunction "PA9_43") (pintype "bidirectional"))
    )
    (net (code "36") (name "/VH_OUT") (class "Default")
      (node (ref "Q3") (pin "1") (pinfunction "G_1") (pintype "passive"))
      (node (ref "R10") (pin "1") (pintype "passive"))
      (node (ref "R29") (pin "2") (pintype "passive"))
    )
    (net (code "37") (name "/VL_IN") (class "Default")
      (node (ref "R2") (pin "2") (pintype "passive"))
      (node (ref "U2") (pin "42") (pinfunction "PA8_42") (pintype "bidirectional"))
    )
    (net (code "38") (name "/VL_OUT") (class "Default")
      (node (ref "Q5") (pin "1") (pinfunction "G_1") (pintype "passive"))
      (node (ref "R13") (pin "1") (pintype "passive"))
      (node (ref "R33") (pin "2") (pintype "passive"))
    )
    (net (code "39") (name "/VOL_SAMP") (class "Default")
      (node (ref "C8") (pin "1") (pinfunction "1_1") (pintype "passive"))
      (node (ref "R21") (pin "2") (pintype "passive"))
      (node (ref "U2") (pin "37") (pinfunction "PB15_37") (pintype "bidirectional"))
    )
    (net (code "40") (name "/V_OUT") (class "Default")
      (node (ref "J8") (pin "1") (pinfunction "1_1") (pintype "passive"))
      (node (ref "R24") (pin "2") (pintype "passive"))
      (node (ref "U7") (pin "1") (pinfunction "IN-_1") (pintype "passive"))
    )
    (net (code "41") (name "/WH_IN") (class "Default")
      (node (ref "R8") (pin "2") (pintype "passive"))
      (node (ref "U2") (pin "41") (pinfunction "PC9_41") (pintype "bidirectional"))
    )
    (net (code "42") (name "/WH_OUT") (class "Default")
      (node (ref "Q2") (pin "1") (pinfunction "G_1") (pintype "passive"))
      (node (ref "R11") (pin "1") (pintype "passive"))
      (node (ref "R7") (pin "2") (pintype "passive"))
    )
    (net (code "43") (name "/WL_IN") (class "Default")
      (node (ref "R3") (pin "2") (pintype "passive"))
      (node (ref "U2") (pin "40") (pinfunction "PC8_40") (pintype "bidirectional"))
    )
    (net (code "44") (name "/WL_OUT") (class "Default")
      (node (ref "Q6") (pin "1") (pinfunction "G_1") (pintype "passive"))
      (node (ref "R14") (pin "1") (pintype "passive"))
      (node (ref "R35") (pin "2") (pintype "passive"))
    )
    (net (code "45") (name "/W_OUT") (class "Default")
      (node (ref "J9") (pin "1") (pinfunction "1_1") (pintype "passive"))
      (node (ref "R23") (pin "2") (pintype "passive"))
      (node (ref "U5") (pin "1") (pinfunction "IN-_1") (pintype "passive"))
    )
    (net (code "46") (name "3V3") (class "Default")
      (node (ref "C48") (pin "2") (pinfunction "2_2") (pintype "passive"))
      (node (ref "C49") (pin "2") (pinfunction "2_2") (pintype "passive"))
      (node (ref "C55") (pin "1") (pinfunction "1_1") (pintype "passive"))
      (node (ref "C56") (pin "1") (pinfunction "1_1") (pintype "passive"))
      (node (ref "C57") (pin "1") (pinfunction "1_1") (pintype "passive"))
      (node (ref "C58") (pin "1") (pinfunction "1_1") (pintype "passive"))
      (node (ref "C59") (pin "1") (pinfunction "1_1") (pintype "passive"))
      (node (ref "C60") (pin "1") (pinfunction "1_1") (pintype "passive"))
      (node (ref "C64") (pin "1") (pinfunction "1_1") (pintype "passive"))
      (node (ref "C65") (pin "1") (pinfunction "1_1") (pintype "passive"))
      (node (ref "J3") (pin "5") (pinfunction "5_5") (pintype "passive"))
      (node (ref "J4") (pin "1") (pinfunction "1_1") (pintype "passive"))
      (node (ref "R26") (pin "2") (pintype "passive"))
      (node (ref "R28") (pin "2") (pintype "passive"))
      (node (ref "R48") (pin "1") (pintype "passive"))
      (node (ref "R55") (pin "2") (pintype "passive"))
      (node (ref "U11") (pin "2") (pinfunction "OUT_2") (pintype "passive"))
      (node (ref "U11") (pin "4") (pinfunction "OUT_4") (pintype "passive"))
      (node (ref "U2") (pin "1") (pinfunction "VBAT_1") (pintype "power_in"))
      (node (ref "U2") (pin "16") (pinfunction "VDD_16") (pintype "power_in"))
      (node (ref "U2") (pin "32") (pinfunction "VDD_32") (pintype "power_in"))
      (node (ref "U2") (pin "48") (pinfunction "VDD_48") (pintype "power_in"))
      (node (ref "U2") (pin "64") (pinfunction "VDD_64") (pintype "power_in"))
      (node (ref "U3") (pin "3") (pinfunction "VDD_3") (pintype "passive"))
      (node (ref "U4") (pin "8") (pinfunction "VCC_8") (pintype "passive"))
    )
    (net (code "47") (name "5V") (class "Default")
      (node (ref "C40") (pin "1") (pinfunction "1_1") (pintype "passive"))
      (node (ref "C41") (pin "1") (pinfunction "1_1") (pintype "passive"))
      (node (ref "C42") (pin "1") (pinfunction "1_1") (pintype "passive"))
      (node (ref "C46") (pin "2") (pinfunction "2_2") (pintype "passive"))
      (node (ref "C47") (pin "2") (pinfunction "2_2") (pintype "passive"))
      (node (ref "C54") (pin "2") (pinfunction "2_2") (pintype "passive"))
      (node (ref "J5") (pin "1") (pinfunction "1_1") (pintype "passive"))
      (node (ref "L2") (pin "2") (pinfunction "2_2") (pintype "passive"))
      (node (ref "R46") (pin "2") (pintype "passive"))
      (node (ref "R50") (pin "1") (pintype "passive"))
      (node (ref "U11") (pin "3") (pinfunction "IN_3") (pintype "passive"))
      (node (ref "U12") (pin "1") (pinfunction "VIN_1") (pintype "passive"))
    )
    (net (code "48") (name "15V") (class "Default")
      (node (ref "C1") (pin "1") (pinfunction "1_1") (pintype "passive"))
      (node (ref "C33") (pin "1") (pinfunction "1_1") (pintype "passive"))
      (node (ref "C34") (pin "1") (pinfunction "1_1") (pintype "passive"))
      (node (ref "C35") (pin "1") (pinfunction "1_1") (pintype "passive"))
      (node (ref "C36") (pin "1") (pinfunction "1_1") (pintype "passive"))
      (node (ref "C43") (pin "1") (pinfunction "1_1") (pintype "passive"))
      (node (ref "C44") (pin "1") (pinfunction "1_1") (pintype "passive"))
      (node (ref "C45") (pin "1") (pinfunction "1_1") (pintype "passive"))
      (node (ref "C66") (pin "1") (pinfunction "1_1") (pintype "passive"))
      (node (ref "C67") (pin "1") (pinfunction "1_1") (pintype "passive"))
      (node (ref "L1") (pin "2") (pinfunction "2_2") (pintype "passive"))
      (node (ref "R36") (pin "2") (pintype "passive"))
      (node (ref "R37") (pin "2") (pintype "passive"))
      (node (ref "R38") (pin "2") (pintype "passive"))
      (node (ref "R39") (pin "2") (pintype "passive"))
      (node (ref "R45") (pin "2") (pintype "passive"))
      (node (ref "U1") (pin "4") (pinfunction "VCC_4") (pintype "passive"))
      (node (ref "U10") (pin "5") (pinfunction "IN_5") (pintype "passive"))
    )
    (net (code "49") (name "AD_3V3") (class "Default")
      (node (ref "C10") (pin "1") (pinfunction "1_1") (pintype "passive"))
      (node (ref "C4") (pin "1") (pinfunction "1_1") (pintype "passive"))
      (node (ref "C53") (pin "2") (pinfunction "2_2") (pintype "passive"))
      (node (ref "C6") (pin "1") (pinfunction "1_1") (pintype "passive"))
      (node (ref "C61") (pin "1") (pinfunction "1_1") (pintype "passive"))
      (node (ref "C62") (pin "1") (pinfunction "1_1") (pintype "passive"))
      (node (ref "C63") (pin "1") (pinfunction "1_1") (pintype "passive"))
      (node (ref "C68") (pin "1") (pinfunction "1_1") (pintype "passive"))
      (node (ref "C69") (pin "1") (pinfunction "1_1") (pintype "passive"))
      (node (ref "C7") (pin "1") (pinfunction "1_1") (pintype "passive"))
      (node (ref "C70") (pin "1") (pinfunction "1_1") (pintype "passive"))
      (node (ref "C71") (pin "1") (pinfunction "1_1") (pintype "passive"))
      (node (ref "U12") (pin "5") (pinfunction "VOUT_5") (pintype "passive"))
      (node (ref "U2") (pin "28") (pinfunction "VREF+_28") (pintype "power_in"))
      (node (ref "U2") (pin "29") (pinfunction "VDDA_29") (pintype "power_in"))
      (node (ref "U5") (pin "3") (pinfunction "REF2_3") (pintype "passive"))
      (node (ref "U5") (pin "6") (pinfunction "VS_6") (pintype "passive"))
      (node (ref "U6") (pin "3") (pinfunction "REF2_3") (pintype "passive"))
      (node (ref "U6") (pin "6") (pinfunction "VS_6") (pintype "passive"))
      (node (ref "U7") (pin "3") (pinfunction "REF2_3") (pintype "passive"))
      (node (ref "U7") (pin "6") (pinfunction "VS_6") (pintype "passive"))
      (node (ref "U8") (pin "6") (pinfunction "VS_6") (pintype "passive"))
    )
    (net (code "50") (name "GND") (class "Default")
      (node (ref "C1") (pin "2") (pinfunction "2_2") (pintype "passive"))
      (node (ref "C10") (pin "2") (pinfunction "2_2") (pintype "passive"))
      (node (ref "C2") (pin "2") (pinfunction "2_2") (pintype "passive"))
      (node (ref "C28") (pin "2") (pinfunction "2_2") (pintype "passive"))
      (node (ref "C29") (pin "2") (pinfunction "2_2") (pintype "passive"))
      (node (ref "C3") (pin "2") (pinfunction "2_2") (pintype "passive"))
      (node (ref "C30") (pin "2") (pinfunction "2_2") (pintype "passive"))
      (node (ref "C31") (pin "2") (pinfunction "2_2") (pintype "passive"))
      (node (ref "C32") (pin "2") (pinfunction "2_2") (pintype "passive"))
      (node (ref "C33") (pin "2") (pinfunction "2_2") (pintype "passive"))
      (node (ref "C34") (pin "2") (pinfunction "2_2") (pintype "passive"))
      (node (ref "C35") (pin "2") (pinfunction "2_2") (pintype "passive"))
      (node (ref "C36") (pin "2") (pinfunction "2_2") (pintype "passive"))
      (node (ref "C37") (pin "2") (pinfunction "2_2") (pintype "passive"))
      (node (ref "C38") (pin "2") (pinfunction "2_2") (pintype "passive"))
      (node (ref "C4") (pin "2") (pinfunction "2_2") (pintype "passive"))
      (node (ref "C40") (pin "2") (pinfunction "2_2") (pintype "passive"))
      (node (ref "C41") (pin "2") (pinfunction "2_2") (pintype "passive"))
      (node (ref "C42") (pin "2") (pinfunction "2_2") (pintype "passive"))
      (node (ref "C43") (pin "2") (pinfunction "2_2") (pintype "passive"))
      (node (ref "C44") (pin "2") (pinfunction "2_2") (pintype "passive"))
      (node (ref "C45") (pin "2") (pinfunction "2_2") (pintype "passive"))
      (node (ref "C46") (pin "1") (pinfunction "1_1") (pintype "passive"))
      (node (ref "C47") (pin "1") (pinfunction "1_1") (pintype "passive"))
      (node (ref "C48") (pin "1") (pinfunction "1_1") (pintype "passive"))
      (node (ref "C49") (pin "1") (pinfunction "1_1") (pintype "passive"))
      (node (ref "C5") (pin "2") (pinfunction "2_2") (pintype "passive"))
      (node (ref "C50") (pin "2") (pinfunction "2_2") (pintype "passive"))
      (node (ref "C51") (pin "1") (pinfunction "1_1") (pintype "passive"))
      (node (ref "C52") (pin "1") (pinfunction "1_1") (pintype "passive"))
      (node (ref "C53") (pin "1") (pinfunction "1_1") (pintype "passive"))
      (node (ref "C54") (pin "1") (pinfunction "1_1") (pintype "passive"))
      (node (ref "C55") (pin "2") (pinfunction "2_2") (pintype "passive"))
      (node (ref "C56") (pin "2") (pinfunction "2_2") (pintype "passive"))
      (node (ref "C57") (pin "2") (pinfunction "2_2") (pintype "passive"))
      (node (ref "C58") (pin "2") (pinfunction "2_2") (pintype "passive"))
      (node (ref "C59") (pin "2") (pinfunction "2_2") (pintype "passive"))
      (node (ref "C6") (pin "2") (pinfunction "2_2") (pintype "passive"))
      (node (ref "C60") (pin "2") (pinfunction "2_2") (pintype "passive"))
      (node (ref "C61") (pin "2") (pinfunction "2_2") (pintype "passive"))
      (node (ref "C62") (pin "2") (pinfunction "2_2") (pintype "passive"))
      (node (ref "C63") (pin "2") (pinfunction "2_2") (pintype "passive"))
      (node (ref "C64") (pin "2") (pinfunction "2_2") (pintype "passive"))
      (node (ref "C65") (pin "2") (pinfunction "2_2") (pintype "passive"))
      (node (ref "C66") (pin "2") (pinfunction "2_2") (pintype "passive"))
      (node (ref "C67") (pin "2") (pinfunction "2_2") (pintype "passive"))
      (node (ref "C68") (pin "2") (pinfunction "2_2") (pintype "passive"))
      (node (ref "C69") (pin "2") (pinfunction "2_2") (pintype "passive"))
      (node (ref "C7") (pin "2") (pinfunction "2_2") (pintype "passive"))
      (node (ref "C70") (pin "2") (pinfunction "2_2") (pintype "passive"))
      (node (ref "C71") (pin "2") (pinfunction "2_2") (pintype "passive"))
      (node (ref "C8") (pin "2") (pinfunction "2_2") (pintype "passive"))
      (node (ref "C9") (pin "2") (pinfunction "2_2") (pintype "passive"))
      (node (ref "D11") (pin "1") (pinfunction "1_1") (pintype "passive"))
      (node (ref "D12") (pin "1") (pinfunction "1_1") (pintype "passive"))
      (node (ref "D13") (pin "3") (pinfunction "3_3") (pintype "passive"))
      (node (ref "D2") (pin "1") (pinfunction "A_1") (pintype "passive"))
      (node (ref "D21") (pin "1") (pinfunction "A_1") (pintype "passive"))
      (node (ref "D22") (pin "1") (pinfunction "A_1") (pintype "passive"))
      (node (ref "J3") (pin "6") (pinfunction "6_6") (pintype "passive"))
      (node (ref "J4") (pin "2") (pinfunction "2_2") (pintype "passive"))
      (node (ref "J5") (pin "2") (pinfunction "2_2") (pintype "passive"))
      (node (ref "R16") (pin "1") (pintype "passive"))
      (node (ref "R41") (pin "1") (pintype "passive"))
      (node (ref "R42") (pin "1") (pintype "passive"))
      (node (ref "R44") (pin "1") (pintype "passive"))
      (node (ref "R47") (pin "2") (pintype "passive"))
      (node (ref "R49") (pin "1") (pintype "passive"))
      (node (ref "R5") (pin "1") (pintype "passive"))
      (node (ref "R51") (pin "2") (pintype "passive"))
      (node (ref "U1") (pin "25") (pinfunction "PAD_25") (pintype "passive"))
      (node (ref "U1") (pin "6") (pinfunction "GND_6") (pintype "passive"))
      (node (ref "U10") (pin "2") (pinfunction "GND_2") (pintype "passive"))
      (node (ref "U11") (pin "1") (pinfunction "ADJ_1") (pintype "passive"))
      (node (ref "U12") (pin "2") (pinfunction "GND_2") (pintype "passive"))
      (node (ref "U2") (pin "15") (pinfunction "VSS_15") (pintype "passive"))
      (node (ref "U2") (pin "27") (pinfunction "VSSA_27") (pintype "passive"))
      (node (ref "U2") (pin "31") (pinfunction "VSS_31") (pintype "passive"))
      (node (ref "U2") (pin "47") (pinfunction "VSS_47") (pintype "passive"))
      (node (ref "U2") (pin "63") (pinfunction "VSS_63") (pintype "passive"))
      (node (ref "U3") (pin "2") (pinfunction "VSS_2") (pintype "passive"))
      (node (ref "U4") (pin "5") (pinfunction "GND_5") (pintype "passive"))
      (node (ref "U5") (pin "2") (pinfunction "GND_2") (pintype "passive"))
      (node (ref "U5") (pin "7") (pinfunction "REF1_7") (pintype "passive"))
      (node (ref "U6") (pin "2") (pinfunction "GND_2") (pintype "passive"))
      (node (ref "U6") (pin "7") (pinfunction "REF1_7") (pintype "passive"))
      (node (ref "U7") (pin "2") (pinfunction "GND_2") (pintype "passive"))
      (node (ref "U7") (pin "7") (pinfunction "REF1_7") (pintype "passive"))
      (node (ref "U8") (pin "2") (pinfunction "GND_2") (pintype "passive"))
      (node (ref "U8") (pin "3") (pinfunction "REF2_3") (pintype "passive"))
      (node (ref "U8") (pin "7") (pinfunction "REF1_7") (pintype "passive"))
      (node (ref "U9") (pin "0") (pinfunction "PAD_0") (pintype "passive"))
      (node (ref "U9") (pin "9") (pinfunction "GND_9") (pintype "passive"))
      (node (ref "X1") (pin "2") (pinfunction "GND_2") (pintype "passive"))
      (node (ref "X1") (pin "4") (pinfunction "GND_4") (pintype "passive"))
    )
    (net (code "51") (name "Net-(C38-Pad1)") (class "Default")
      (node (ref "C38") (pin "1") (pinfunction "1_1") (pintype "passive"))
      (node (ref "R43") (pin "1") (pintype "passive"))
    )
    (net (code "52") (name "Net-(D1-Pad1)") (class "Default")
      (node (ref "D1") (pin "1") (pinfunction "1_1") (pintype "passive"))
      (node (ref "R26") (pin "1") (pintype "passive"))
    )
    (net (code "53") (name "Net-(D2-K)") (class "Default")
      (node (ref "D2") (pin "2") (pinfunction "K_2") (pintype "passive"))
      (node (ref "R15") (pin "1") (pintype "passive"))
      (node (ref "R16") (pin "2") (pintype "passive"))
      (node (ref "R21") (pin "1") (pintype "passive"))
    )
    (net (code "54") (name "Net-(D3-Pad1)") (class "Default")
      (node (ref "D3") (pin "1") (pinfunction "1_1") (pintype "passive"))
      (node (ref "R28") (pin "1") (pintype "passive"))
    )
    (net (code "55") (name "Net-(D8-Pad1)") (class "Default")
      (node (ref "D8") (pin "1") (pinfunction "1_1") (pintype "passive"))
      (node (ref "R36") (pin "1") (pintype "passive"))
    )
    (net (code "56") (name "Net-(D9-Pad1)") (class "Default")
      (node (ref "D9") (pin "1") (pinfunction "1_1") (pintype "passive"))
      (node (ref "R37") (pin "1") (pintype "passive"))
    )
    (net (code "57") (name "Net-(D10-Pad1)") (class "Default")
      (node (ref "D10") (pin "1") (pinfunction "1_1") (pintype "passive"))
      (node (ref "R38") (pin "1") (pintype "passive"))
    )
    (net (code "58") (name "Net-(J3-Pad1)") (class "Default")
      (node (ref "J3") (pin "1") (pinfunction "1_1") (pintype "passive"))
      (node (ref "R58") (pin "1") (pintype "passive"))
    )
    (net (code "59") (name "Net-(J3-Pad2)") (class "Default")
      (node (ref "J3") (pin "2") (pinfunction "2_2") (pintype "passive"))
      (node (ref "R57") (pin "1") (pintype "passive"))
    )
    (net (code "60") (name "Net-(J3-Pad3)") (class "Default")
      (node (ref "J3") (pin "3") (pinfunction "3_3") (pintype "passive"))
      (node (ref "R56") (pin "1") (pintype "passive"))
    )
    (net (code "61") (name "Net-(U1-BOOT1)") (class "Default")
      (node (ref "C11") (pin "1") (pinfunction "1_1") (pintype "passive"))
      (node (ref "D8") (pin "2") (pinfunction "2_2") (pintype "passive"))
      (node (ref "U1") (pin "20") (pinfunction "BOOT1_20") (pintype "passive"))
    )
    (net (code "62") (name "Net-(U1-BOOT2)") (class "Default")
      (node (ref "C12") (pin "1") (pinfunction "1_1") (pintype "passive"))
      (node (ref "D9") (pin "2") (pinfunction "2_2") (pintype "passive"))
      (node (ref "U1") (pin "17") (pinfunction "BOOT2_17") (pintype "passive"))
    )
    (net (code "63") (name "Net-(U1-BOOT3)") (class "Default")
      (node (ref "C13") (pin "1") (pinfunction "1_1") (pintype "passive"))
      (node (ref "D10") (pin "2") (pinfunction "2_2") (pintype "passive"))
      (node (ref "U1") (pin "14") (pinfunction "BOOT3_14") (pintype "passive"))
    )
    (net (code "64") (name "Net-(U1-HIN1)") (class "Default")
      (node (ref "R4") (pin "1") (pintype "passive"))
      (node (ref "U1") (pin "22") (pinfunction "HIN1_22") (pintype "passive"))
    )
    (net (code "65") (name "Net-(U1-HIN2)") (class "Default")
      (node (ref "R6") (pin "1") (pintype "passive"))
      (node (ref "U1") (pin "23") (pinfunction "HIN2_23") (pintype "passive"))
    )
    (net (code "66") (name "Net-(U1-HIN3)") (class "Default")
      (node (ref "R8") (pin "1") (pintype "passive"))
      (node (ref "U1") (pin "24") (pinfunction "HIN3_24") (pintype "passive"))
    )
    (net (code "67") (name "Net-(U1-HO1)") (class "Default")
      (node (ref "R27") (pin "1") (pintype "passive"))
      (node (ref "U1") (pin "19") (pinfunction "HO1_19") (pintype "passive"))
    )
    (net (code "68") (name "Net-(U1-HO2)") (class "Default")
      (node (ref "R29") (pin "1") (pintype "passive"))
      (node (ref "U1") (pin "16") (pinfunction "HO2_16") (pintype "passive"))
    )
    (net (code "69") (name "Net-(U1-HO3)") (class "Default")
      (node (ref "R7") (pin "1") (pintype "passive"))
      (node (ref "U1") (pin "13") (pinfunction "HO3_13") (pintype "passive"))
    )
    (net (code "70") (name "Net-(U1-LIN1)") (class "Default")
      (node (ref "R1") (pin "1") (pintype "passive"))
      (node (ref "U1") (pin "1") (pinfunction "LIN1_1") (pintype "passive"))
    )
    (net (code "71") (name "Net-(U1-LIN2)") (class "Default")
      (node (ref "R2") (pin "1") (pintype "passive"))
      (node (ref "U1") (pin "2") (pinfunction "LIN2_2") (pintype "passive"))
    )
    (net (code "72") (name "Net-(U1-LIN3)") (class "Default")
      (node (ref "R3") (pin "1") (pintype "passive"))
      (node (ref "U1") (pin "3") (pinfunction "LIN3_3") (pintype "passive"))
    )
    (net (code "73") (name "Net-(U1-LO1)") (class "Default")
      (node (ref "R31") (pin "1") (pintype "passive"))
      (node (ref "U1") (pin "11") (pinfunction "LO1_11") (pintype "passive"))
    )
    (net (code "74") (name "Net-(U1-LO2)") (class "Default")
      (node (ref "R33") (pin "1") (pintype "passive"))
      (node (ref "U1") (pin "10") (pinfunction "LO2_10") (pintype "passive"))
    )
    (net (code "75") (name "Net-(U1-LO3)") (class "Default")
      (node (ref "R35") (pin "1") (pintype "passive"))
      (node (ref "U1") (pin "9") (pinfunction "LO3_9") (pintype "passive"))
    )
    (net (code "76") (name "Net-(U2A-PG10-NRST)") (class "Default")
      (node (ref "C50") (pin "1") (pinfunction "1_1") (pintype "passive"))
      (node (ref "R48") (pin "2") (pintype "passive"))
      (node (ref "U2") (pin "7") (pinfunction "PG10-NRST_7") (pintype "bidirectional"))
    )
    (net (code "77") (name "Net-(U3-RS)") (class "Default")
      (node (ref "R51") (pin "1") (pintype "passive"))
      (node (ref "U3") (pin "8") (pinfunction "RS_8") (pintype "passive"))
    )
    (net (code "78") (name "Net-(U5-OUT)") (class "Default")
      (node (ref "R18") (pin "2") (pintype "passive"))
      (node (ref "U5") (pin "5") (pinfunction "OUT_5") (pintype "passive"))
    )
    (net (code "79") (name "Net-(U6-OUT)") (class "Default")
      (node (ref "R19") (pin "2") (pintype "passive"))
      (node (ref "U6") (pin "5") (pinfunction "OUT_5") (pintype "passive"))
    )
    (net (code "80") (name "Net-(U7-OUT)") (class "Default")
      (node (ref "R20") (pin "2") (pintype "passive"))
      (node (ref "U7") (pin "5") (pinfunction "OUT_5") (pintype "passive"))
    )
    (net (code "81") (name "Net-(U8-OUT)") (class "Default")
      (node (ref "R22") (pin "2") (pintype "passive"))
      (node (ref "U8") (pin "5") (pinfunction "OUT_5") (pintype "passive"))
    )
    (net (code "82") (name "Net-(U9-BOOT)") (class "Default")
      (node (ref "C27") (pin "1") (pinfunction "1_1") (pintype "passive"))
      (node (ref "U9") (pin "1") (pinfunction "BOOT_1") (pintype "passive"))
    )
    (net (code "83") (name "Net-(U9-COMP)") (class "Default")
      (node (ref "C37") (pin "1") (pinfunction "1_1") (pintype "passive"))
      (node (ref "R43") (pin "2") (pintype "passive"))
      (node (ref "U9") (pin "8") (pinfunction "COMP_8") (pintype "passive"))
    )
    (net (code "84") (name "Net-(U9-EN)") (class "Default")
      (node (ref "R40") (pin "1") (pintype "passive"))
      (node (ref "R42") (pin "2") (pintype "passive"))
      (node (ref "U9") (pin "3") (pinfunction "EN_3") (pintype "passive"))
    )
    (net (code "85") (name "Net-(U9-RT)") (class "Default")
      (node (ref "R44") (pin "2") (pintype "passive"))
      (node (ref "U9") (pin "5") (pinfunction "RT_5") (pintype "passive"))
    )
    (net (code "86") (name "Net-(U9-SS)") (class "Default")
      (node (ref "C28") (pin "1") (pinfunction "1_1") (pintype "passive"))
      (node (ref "U9") (pin "4") (pinfunction "SS_4") (pintype "passive"))
    )
    (net (code "87") (name "Net-(U9-SW)") (class "Default")
      (node (ref "C27") (pin "2") (pinfunction "2_2") (pintype "passive"))
      (node (ref "D11") (pin "2") (pinfunction "2_2") (pintype "passive"))
      (node (ref "L1") (pin "1") (pinfunction "1_1") (pintype "passive"))
      (node (ref "U9") (pin "10") (pinfunction "SW_10") (pintype "passive"))
    )
    (net (code "88") (name "Net-(U10-BS)") (class "Default")
      (node (ref "C39") (pin "1") (pinfunction "1_1") (pintype "passive"))
      (node (ref "U10") (pin "1") (pinfunction "BS_1") (pintype "passive"))
    )
    (net (code "89") (name "Net-(U10-EN)") (class "Default")
      (node (ref "R45") (pin "1") (pintype "passive"))
      (node (ref "U10") (pin "4") (pinfunction "EN_4") (pintype "passive"))
    )
    (net (code "90") (name "Net-(U10-FB)") (class "Default")
      (node (ref "R46") (pin "1") (pintype "passive"))
      (node (ref "R47") (pin "1") (pintype "passive"))
      (node (ref "U10") (pin "3") (pinfunction "FB_3") (pintype "passive"))
    )
    (net (code "91") (name "Net-(U10-SW)") (class "Default")
      (node (ref "C39") (pin "2") (pinfunction "2_2") (pintype "passive"))
      (node (ref "D12") (pin "2") (pinfunction "2_2") (pintype "passive"))
      (node (ref "L2") (pin "1") (pinfunction "1_1") (pintype "passive"))
      (node (ref "U10") (pin "6") (pinfunction "SW_6") (pintype "passive"))
    )
    (net (code "92") (name "Net-(U12-EN)") (class "Default")
      (node (ref "R50") (pin "2") (pintype "passive"))
      (node (ref "U12") (pin "3") (pinfunction "EN_3") (pintype "passive"))
    )
    (net (code "93") (name "PGND") (class "Default")
      (node (ref "C14") (pin "2") (pinfunction "2_2") (pintype "passive"))
      (node (ref "C15") (pin "2") (pinfunction "2_2") (pintype "passive"))
      (node (ref "C16") (pin "2") (pinfunction "2_2") (pintype "passive"))
      (node (ref "C17") (pin "2") (pinfunction "2_2") (pintype "passive"))
      (node (ref "C18") (pin "2") (pinfunction "2_2") (pintype "passive"))
      (node (ref "C19") (pin "2") (pinfunction "2_2") (pintype "passive"))
      (node (ref "C20") (pin "2") (pinfunction "2_2") (pintype "passive"))
      (node (ref "C21") (pin "2") (pinfunction "2_2") (pintype "passive"))
      (node (ref "C22") (pin "2") (pinfunction "2_2") (pintype "passive"))
      (node (ref "C23") (pin "2") (pinfunction "2_2") (pintype "passive"))
      (node (ref "C24") (pin "2") (pinfunction "2_2") (pintype "passive"))
      (node (ref "C25") (pin "2") (pinfunction "2_2") (pintype "passive"))
      (node (ref "C26") (pin "2") (pinfunction "2_2") (pintype "passive"))
      (node (ref "J2") (pin "2") (pinfunction "2_2") (pintype "passive"))
      (node (ref "Q4") (pin "3") (pinfunction "S_3") (pintype "passive"))
      (node (ref "Q5") (pin "3") (pinfunction "S_3") (pintype "passive"))
      (node (ref "Q6") (pin "3") (pinfunction "S_3") (pintype "passive"))
      (node (ref "R12") (pin "2") (pintype "passive"))
      (node (ref "R13") (pin "2") (pintype "passive"))
      (node (ref "R14") (pin "2") (pintype "passive"))
      (node (ref "R5") (pin "2") (pintype "passive"))
    )
    (net (code "94") (name "VBAT") (class "Default")
      (node (ref "J2") (pin "1") (pinfunction "1_1") (pintype "passive"))
      (node (ref "R17") (pin "1") (pintype "passive"))
      (node (ref "U8") (pin "8") (pinfunction "IN+_8") (pintype "passive"))
    )
    (net (code "95") (name "VIN") (class "Default")
      (node (ref "C14") (pin "1") (pinfunction "1_1") (pintype "passive"))
      (node (ref "C15") (pin "1") (pinfunction "1_1") (pintype "passive"))
      (node (ref "C16") (pin "1") (pinfunction "1_1") (pintype "passive"))
      (node (ref "C17") (pin "1") (pinfunction "1_1") (pintype "passive"))
      (node (ref "C18") (pin "1") (pinfunction "1_1") (pintype "passive"))
      (node (ref "C19") (pin "1") (pinfunction "1_1") (pintype "passive"))
      (node (ref "C20") (pin "1") (pinfunction "1_1") (pintype "passive"))
      (node (ref "C21") (pin "1") (pinfunction "1_1") (pintype "passive"))
      (node (ref "C22") (pin "1") (pinfunction "1_1") (pintype "passive"))
      (node (ref "C23") (pin "1") (pinfunction "1_1") (pintype "passive"))
      (node (ref "C24") (pin "1") (pinfunction "1_1") (pintype "passive"))
      (node (ref "C25") (pin "1") (pinfunction "1_1") (pintype "passive"))
      (node (ref "C26") (pin "1") (pinfunction "1_1") (pintype "passive"))
      (node (ref "C29") (pin "1") (pinfunction "1_1") (pintype "passive"))
      (node (ref "C30") (pin "1") (pinfunction "1_1") (pintype "passive"))
      (node (ref "C31") (pin "1") (pinfunction "1_1") (pintype "passive"))
      (node (ref "C32") (pin "1") (pinfunction "1_1") (pintype "passive"))
      (node (ref "Q1") (pin "2") (pinfunction "D_2") (pintype "passive"))
      (node (ref "Q2") (pin "2") (pinfunction "D_2") (pintype "passive"))
      (node (ref "Q3") (pin "2") (pinfunction "D_2") (pintype "passive"))
      (node (ref "R15") (pin "2") (pintype "passive"))
      (node (ref "R17") (pin "2") (pintype "passive"))
      (node (ref "R40") (pin "2") (pintype "passive"))
      (node (ref "U8") (pin "1") (pinfunction "IN-_1") (pintype "passive"))
      (node (ref "U9") (pin "2") (pinfunction "VIN_2") (pintype "passive"))
    )
    (net (code "96") (name "unconnected-(U1-NC-Pad5)") (class "Default")
      (node (ref "U1") (pin "5") (pinfunction "NC_5") (pintype "passive"))
    )
    (net (code "97") (name "unconnected-(U1-NC-Pad7)") (class "Default")
      (node (ref "U1") (pin "7") (pinfunction "NC_7") (pintype "passive"))
    )
    (net (code "98") (name "unconnected-(U1-NC-Pad8)") (class "Default")
      (node (ref "U1") (pin "8") (pinfunction "NC_8") (pintype "passive"))
    )
    (net (code "99") (name "unconnected-(U1-NC-Pad21)") (class "Default")
      (node (ref "U1") (pin "21") (pinfunction "NC_21") (pintype "passive"))
    )
    (net (code "100") (name "unconnected-(U2A-PA0-Pad12)") (class "Default")
      (node (ref "U2") (pin "12") (pinfunction "PA0_12") (pintype "bidirectional"))
    )
    (net (code "101") (name "unconnected-(U2A-PA1-Pad13)") (class "Default")
      (node (ref "U2") (pin "13") (pinfunction "PA1_13") (pintype "bidirectional"))
    )
    (net (code "102") (name "unconnected-(U2A-PA2-Pad14)") (class "Default")
      (node (ref "U2") (pin "14") (pinfunction "PA2_14") (pintype "bidirectional"))
    )
    (net (code "103") (name "unconnected-(U2A-PA3-Pad17)") (class "Default")
      (node (ref "U2") (pin "17") (pinfunction "PA3_17") (pintype "bidirectional"))
    )
    (net (code "104") (name "unconnected-(U2A-PA4-Pad18)") (class "Default")
      (node (ref "U2") (pin "18") (pinfunction "PA4_18") (pintype "bidirectional"))
    )
    (net (code "105") (name "unconnected-(U2A-PA5-Pad19)") (class "Default")
      (node (ref "U2") (pin "19") (pinfunction "PA5_19") (pintype "bidirectional"))
    )
    (net (code "106") (name "unconnected-(U2A-PA6-Pad20)") (class "Default")
      (node (ref "U2") (pin "20") (pinfunction "PA6_20") (pintype "bidirectional"))
    )
    (net (code "107") (name "unconnected-(U2A-PA7-Pad21)") (class "Default")
      (node (ref "U2") (pin "21") (pinfunction "PA7_21") (pintype "bidirectional"))
    )
    (net (code "108") (name "unconnected-(U2A-PA12-Pad46)") (class "Default")
      (node (ref "U2") (pin "46") (pinfunction "PA12_46") (pintype "bidirectional"))
    )
    (net (code "109") (name "unconnected-(U2A-PB10-Pad30)") (class "Default")
      (node (ref "U2") (pin "30") (pinfunction "PB10_30") (pintype "bidirectional"))
    )
    (net (code "110") (name "unconnected-(U2A-PB11-Pad33)") (class "Default")
      (node (ref "U2") (pin "33") (pinfunction "PB11_33") (pintype "bidirectional"))
    )
    (net (code "111") (name "unconnected-(U2A-PB12-Pad34)") (class "Default")
      (node (ref "U2") (pin "34") (pinfunction "PB12_34") (pintype "bidirectional"))
    )
    (net (code "112") (name "unconnected-(U2A-PB13-Pad35)") (class "Default")
      (node (ref "U2") (pin "35") (pinfunction "PB13_35") (pintype "bidirectional"))
    )
    (net (code "113") (name "unconnected-(U2A-PC0-Pad8)") (class "Default")
      (node (ref "U2") (pin "8") (pinfunction "PC0_8") (pintype "bidirectional"))
    )
    (net (code "114") (name "unconnected-(U2A-PC1-Pad9)") (class "Default")
      (node (ref "U2") (pin "9") (pinfunction "PC1_9") (pintype "bidirectional"))
    )
    (net (code "115") (name "unconnected-(U2A-PC2-Pad10)") (class "Default")
      (node (ref "U2") (pin "10") (pinfunction "PC2_10") (pintype "bidirectional"))
    )
    (net (code "116") (name "unconnected-(U2A-PC3-Pad11)") (class "Default")
      (node (ref "U2") (pin "11") (pinfunction "PC3_11") (pintype "bidirectional"))
    )
    (net (code "117") (name "unconnected-(U2A-PC4-Pad22)") (class "Default")
      (node (ref "U2") (pin "22") (pinfunction "PC4_22") (pintype "bidirectional"))
    )
    (net (code "118") (name "unconnected-(U2A-PC5-Pad23)") (class "Default")
      (node (ref "U2") (pin "23") (pinfunction "PC5_23") (pintype "bidirectional"))
    )
    (net (code "119") (name "unconnected-(U2A-PC6-Pad38)") (class "Default")
      (node (ref "U2") (pin "38") (pinfunction "PC6_38") (pintype "bidirectional"))
    )
    (net (code "120") (name "unconnected-(U2A-PC7-Pad39)") (class "Default")
      (node (ref "U2") (pin "39") (pinfunction "PC7_39") (pintype "bidirectional"))
    )
    (net (code "121") (name "unconnected-(U2A-PC13-Pad2)") (class "Default")
      (node (ref "U2") (pin "2") (pinfunction "PC13_2") (pintype "bidirectional"))
    )
    (net (code "122") (name "unconnected-(U2A-PD2-Pad55)") (class "Default")
      (node (ref "U2") (pin "55") (pinfunction "PD2_55") (pintype "bidirectional"))
    )
    (net (code "123") (name "unconnected-(U3-Vref-Pad5)") (class "Default")
      (node (ref "U3") (pin "5") (pinfunction "Vref_5") (pintype "passive"))
    )
    (net (code "124") (name "unconnected-(U5-NC-Pad4)") (class "Default")
      (node (ref "U5") (pin "4") (pinfunction "NC_4") (pintype "passive"))
    )
    (net (code "125") (name "unconnected-(U6-NC-Pad4)") (class "Default")
      (node (ref "U6") (pin "4") (pinfunction "NC_4") (pintype "passive"))
    )
    (net (code "126") (name "unconnected-(U7-NC-Pad4)") (class "Default")
      (node (ref "U7") (pin "4") (pinfunction "NC_4") (pintype "passive"))
    )
    (net (code "127") (name "unconnected-(U8-NC-Pad4)") (class "Default")
      (node (ref "U8") (pin "4") (pinfunction "NC_4") (pintype "passive"))
    )
    (net (code "128") (name "unconnected-(U9-PWRGD-Pad6)") (class "Default")
      (node (ref "U9") (pin "6") (pinfunction "PWRGD_6") (pintype "passive"))
    )
    (net (code "129") (name "unconnected-(U12-BYP-Pad4)") (class "Default")
      (node (ref "U12") (pin "4") (pinfunction "BYP_4") (pintype "passive"))
    )
  )
)
